# DAAP.net
KiCad netlist of a schematic drawn in EasyEDA
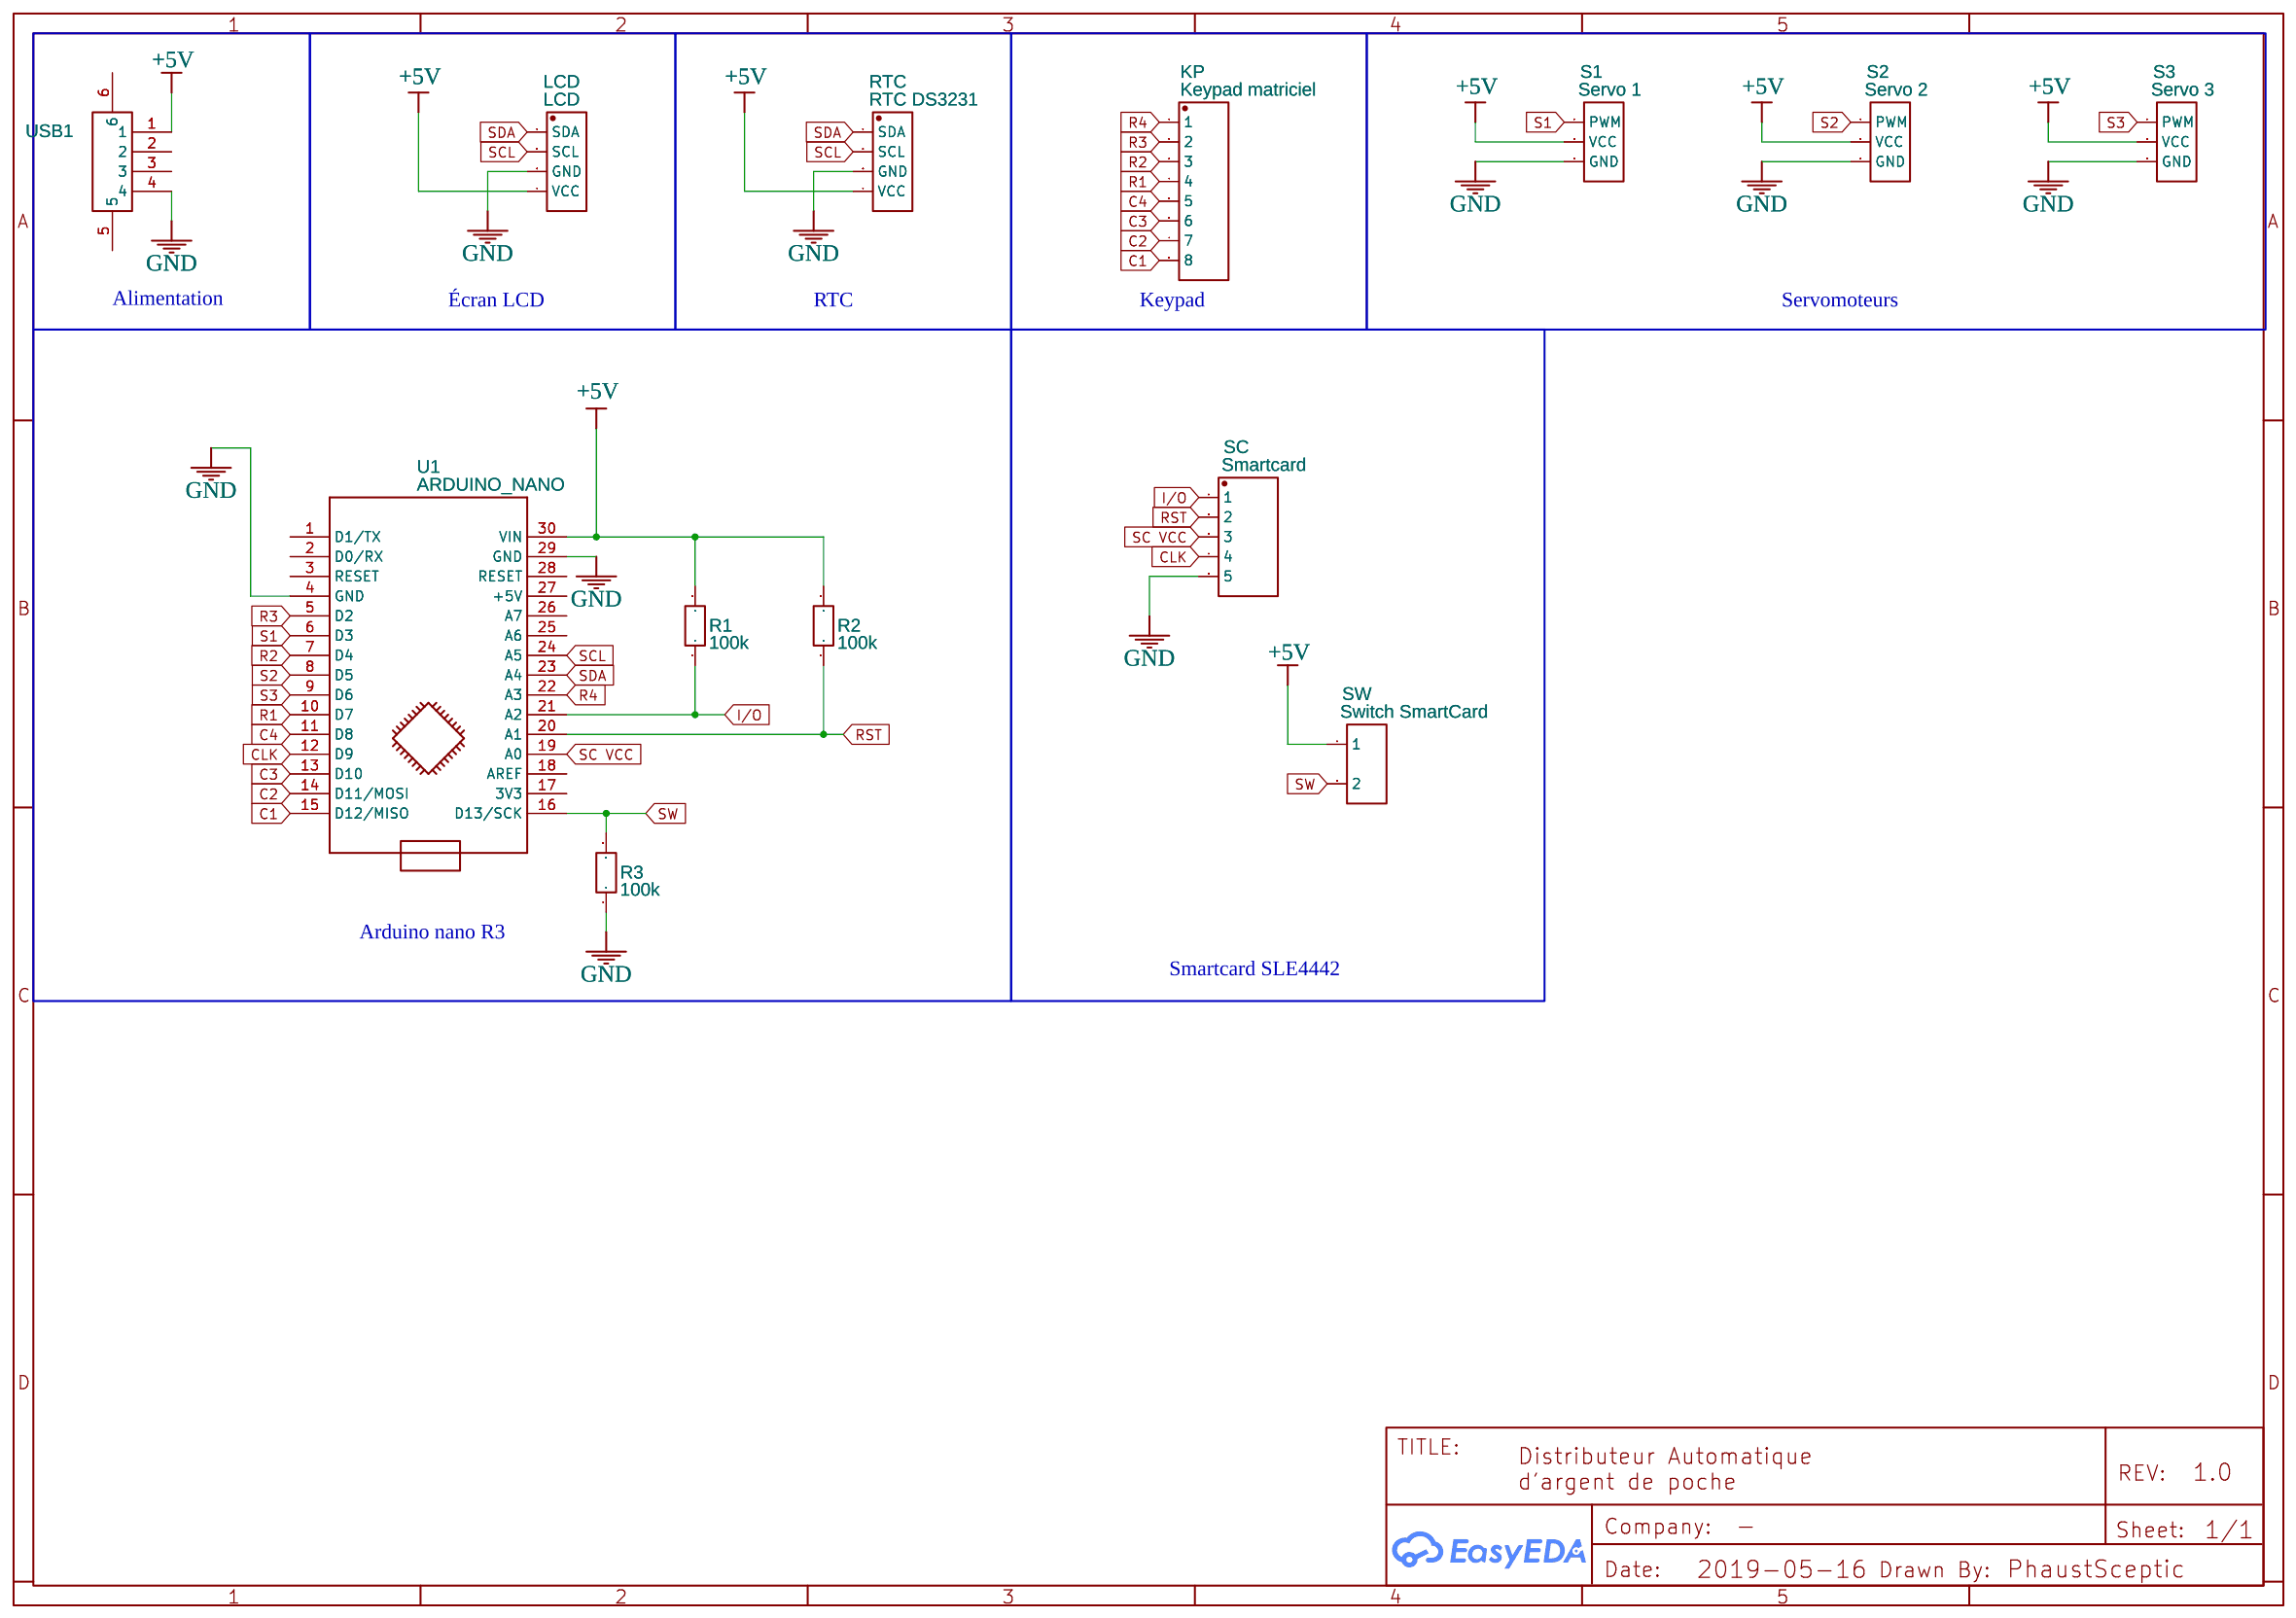
[diagram p0: schematic sheet]

(export (version "E")
  (design (tool "Eeschema 10.0.6"))
  (components
    (comp (ref "KP")
      (value "Keypad matriciel")
      (fields
        (field (name "BOM_Manufacturer Part") "210S-1*8P L=11.6MMGold-plated black")
        (field (name "BOM_Supplier Part") "C124381")
      )
      (libsource (lib "") (part "Unknown_600_90"))
    )
    (comp (ref "LCD")
      (value "LCD")
      (fields
        (field (name "BOM_Manufacturer Part") "210S-1*4P L=11.6MMGold-plated black")
        (field (name "BOM_Supplier Part") "C124378")
      )
      (libsource (lib "") (part "Unknown_275_75"))
    )
    (comp (ref "R1")
      (value "100k")
      (fields (field (name "BOM_Manufacturer Part") "?"))
      (libsource (lib "") (part "Res_AXIAL-0.3(1/8W)_EU"))
    )
    (comp (ref "R2")
      (value "100k")
      (fields (field (name "BOM_Manufacturer Part") "?"))
      (libsource (lib "") (part "Res_AXIAL-0.3(1/8W)_EU"))
    )
    (comp (ref "R3")
      (value "100k")
      (fields (field (name "BOM_Manufacturer Part") "?"))
      (libsource (lib "") (part "Res_AXIAL-0.3(1/8W)_EU"))
    )
    (comp (ref "RTC")
      (value "RTC DS3231")
      (fields
        (field (name "BOM_Manufacturer Part") "210S-1*4P L=11.6MMGold-plated black")
        (field (name "BOM_Supplier Part") "C124378")
      )
      (libsource (lib "") (part "Unknown_440_75"))
    )
    (comp (ref "S1")
      (value "Servo 1")
      (fields
        (field (name "BOM_Manufacturer Part") "Header2.54mm 1*3P")
        (field (name "BOM_Supplier Part") "C49257")
      )
      (libsource (lib "") (part "Unknown_800_65"))
    )
    (comp (ref "S2")
      (value "Servo 2")
      (fields
        (field (name "BOM_Manufacturer Part") "Header2.54mm 1*3P")
        (field (name "BOM_Supplier Part") "C49257")
      )
      (libsource (lib "") (part "Unknown_945_65"))
    )
    (comp (ref "S3")
      (value "Servo 3")
      (fields
        (field (name "BOM_Manufacturer Part") "Header2.54mm 1*3P")
        (field (name "BOM_Supplier Part") "C49257")
      )
      (libsource (lib "") (part "Unknown_1090_65"))
    )
    (comp (ref "SC")
      (value "Smartcard")
      (fields
        (field (name "BOM_Manufacturer Part") "210S-1*5P L=11.6MMGold-plated black")
        (field (name "BOM_Supplier Part") "C124379")
      )
      (libsource (lib "") (part "Unknown_620_265"))
    )
    (comp (ref "SW")
      (value "Switch SmartCard")
      (fields (field (name "BOM_Manufacturer Part") "826629-2") (field (name "BOM_Supplier Part") "C86471"))
      (libsource (lib "") (part "Unknown_680_380"))
    )
    (comp (ref "U1")
      (value "ARDUINO_NANO")
      (fields (field (name "BOM_Manufacturer Part") "?"))
      (libsource (lib "") (part "Unknown_210_340"))
    )
    (comp (ref "USB1")
      (value "USB-AF-90-14.4X13.6-H7.0-DIP")
      (fields (field (name "BOM_Supplier Part") "C46407"))
      (libsource (lib "") (part "Unknown_50_70"))
    )
  )
  (nets
    (net (code "1") (name "+5V") (class "Default")
      (node (ref "LCD") (pin "4") (pinfunction "VCC_4") (pintype "unspecified"))
      (node (ref "R1") (pin "2") (pinfunction "2_2") (pintype "unspecified"))
      (node (ref "R2") (pin "2") (pinfunction "2_2") (pintype "unspecified"))
      (node (ref "RTC") (pin "4") (pinfunction "VCC_4") (pintype "unspecified"))
      (node (ref "S1") (pin "2") (pinfunction "VCC_2") (pintype "input"))
      (node (ref "S2") (pin "2") (pinfunction "VCC_2") (pintype "input"))
      (node (ref "S3") (pin "2") (pinfunction "VCC_2") (pintype "input"))
      (node (ref "SW") (pin "1") (pinfunction "1_1") (pintype "unspecified"))
      (node (ref "U1") (pin "30") (pinfunction "VIN_30") (pintype "unspecified"))
      (node (ref "USB1") (pin "1") (pinfunction "1_1") (pintype "unspecified"))
    )
    (net (code "2") (name "C1") (class "Default")
      (node (ref "KP") (pin "8") (pinfunction "8_8") (pintype "unspecified"))
      (node (ref "U1") (pin "15") (pinfunction "D12/MISO_15") (pintype "unspecified"))
    )
    (net (code "3") (name "C2") (class "Default")
      (node (ref "KP") (pin "7") (pinfunction "7_7") (pintype "unspecified"))
      (node (ref "U1") (pin "14") (pinfunction "D11/MOSI_14") (pintype "unspecified"))
    )
    (net (code "4") (name "C3") (class "Default")
      (node (ref "KP") (pin "6") (pinfunction "6_6") (pintype "unspecified"))
      (node (ref "U1") (pin "13") (pinfunction "D10_13") (pintype "unspecified"))
    )
    (net (code "5") (name "C4") (class "Default")
      (node (ref "KP") (pin "5") (pinfunction "5_5") (pintype "unspecified"))
      (node (ref "U1") (pin "11") (pinfunction "D8_11") (pintype "unspecified"))
    )
    (net (code "6") (name "CLK") (class "Default")
      (node (ref "SC") (pin "4") (pinfunction "4_4") (pintype "unspecified"))
      (node (ref "U1") (pin "12") (pinfunction "D9_12") (pintype "unspecified"))
    )
    (net (code "7") (name "GND") (class "Default")
      (node (ref "LCD") (pin "3") (pinfunction "GND_3") (pintype "unspecified"))
      (node (ref "R3") (pin "1") (pinfunction "1_1") (pintype "unspecified"))
      (node (ref "RTC") (pin "3") (pinfunction "GND_3") (pintype "unspecified"))
      (node (ref "S1") (pin "3") (pinfunction "GND_3") (pintype "input"))
      (node (ref "S2") (pin "3") (pinfunction "GND_3") (pintype "input"))
      (node (ref "S3") (pin "3") (pinfunction "GND_3") (pintype "input"))
      (node (ref "SC") (pin "5") (pinfunction "5_5") (pintype "unspecified"))
      (node (ref "U1") (pin "29") (pinfunction "GND_29") (pintype "unspecified"))
      (node (ref "U1") (pin "4") (pinfunction "GND_4") (pintype "unspecified"))
      (node (ref "USB1") (pin "4") (pinfunction "4_4") (pintype "unspecified"))
    )
    (net (code "8") (name "I{slash}O") (class "Default")
      (node (ref "R1") (pin "1") (pinfunction "1_1") (pintype "unspecified"))
      (node (ref "SC") (pin "1") (pinfunction "1_1") (pintype "unspecified"))
      (node (ref "U1") (pin "21") (pinfunction "A2_21") (pintype "unspecified"))
    )
    (net (code "9") (name "R1") (class "Default")
      (node (ref "KP") (pin "4") (pinfunction "4_4") (pintype "unspecified"))
      (node (ref "U1") (pin "10") (pinfunction "D7_10") (pintype "unspecified"))
    )
    (net (code "10") (name "R2") (class "Default")
      (node (ref "KP") (pin "3") (pinfunction "3_3") (pintype "unspecified"))
      (node (ref "U1") (pin "7") (pinfunction "D4_7") (pintype "unspecified"))
    )
    (net (code "11") (name "R3") (class "Default")
      (node (ref "KP") (pin "2") (pinfunction "2_2") (pintype "unspecified"))
      (node (ref "U1") (pin "5") (pinfunction "D2_5") (pintype "unspecified"))
    )
    (net (code "12") (name "R4") (class "Default")
      (node (ref "KP") (pin "1") (pinfunction "1_1") (pintype "unspecified"))
      (node (ref "U1") (pin "22") (pinfunction "A3_22") (pintype "unspecified"))
    )
    (net (code "13") (name "RST") (class "Default")
      (node (ref "R2") (pin "1") (pinfunction "1_1") (pintype "unspecified"))
      (node (ref "SC") (pin "2") (pinfunction "2_2") (pintype "unspecified"))
      (node (ref "U1") (pin "20") (pinfunction "A1_20") (pintype "unspecified"))
    )
    (net (code "14") (name "S1") (class "Default")
      (node (ref "S1") (pin "1") (pinfunction "PWM_1") (pintype "input"))
      (node (ref "U1") (pin "6") (pinfunction "D3_6") (pintype "unspecified"))
    )
    (net (code "15") (name "S2") (class "Default")
      (node (ref "S2") (pin "1") (pinfunction "PWM_1") (pintype "input"))
      (node (ref "U1") (pin "8") (pinfunction "D5_8") (pintype "unspecified"))
    )
    (net (code "16") (name "S3") (class "Default")
      (node (ref "S3") (pin "1") (pinfunction "PWM_1") (pintype "input"))
      (node (ref "U1") (pin "9") (pinfunction "D6_9") (pintype "unspecified"))
    )
    (net (code "17") (name "SC VCC") (class "Default")
      (node (ref "SC") (pin "3") (pinfunction "3_3") (pintype "unspecified"))
      (node (ref "U1") (pin "19") (pinfunction "A0_19") (pintype "unspecified"))
    )
    (net (code "18") (name "SCL") (class "Default")
      (node (ref "LCD") (pin "2") (pinfunction "SCL_2") (pintype "unspecified"))
      (node (ref "RTC") (pin "2") (pinfunction "SCL_2") (pintype "unspecified"))
      (node (ref "U1") (pin "24") (pinfunction "A5_24") (pintype "unspecified"))
    )
    (net (code "19") (name "SDA") (class "Default")
      (node (ref "LCD") (pin "1") (pinfunction "SDA_1") (pintype "unspecified"))
      (node (ref "RTC") (pin "1") (pinfunction "SDA_1") (pintype "unspecified"))
      (node (ref "U1") (pin "23") (pinfunction "A4_23") (pintype "unspecified"))
    )
    (net (code "20") (name "SW") (class "Default")
      (node (ref "R3") (pin "2") (pinfunction "2_2") (pintype "unspecified"))
      (node (ref "SW") (pin "2") (pinfunction "2_2") (pintype "unspecified"))
      (node (ref "U1") (pin "16") (pinfunction "D13/SCK_16") (pintype "unspecified"))
    )
    (net (code "21") (name "unconnected-(U1-+5V-Pad27)") (class "Default")
      (node (ref "U1") (pin "27") (pinfunction "+5V_27") (pintype "unspecified"))
    )
    (net (code "22") (name "unconnected-(U1-3V3-Pad17)") (class "Default")
      (node (ref "U1") (pin "17") (pinfunction "3V3_17") (pintype "unspecified"))
    )
    (net (code "23") (name "unconnected-(U1-A6-Pad25)") (class "Default")
      (node (ref "U1") (pin "25") (pinfunction "A6_25") (pintype "unspecified"))
    )
    (net (code "24") (name "unconnected-(U1-A7-Pad26)") (class "Default")
      (node (ref "U1") (pin "26") (pinfunction "A7_26") (pintype "unspecified"))
    )
    (net (code "25") (name "unconnected-(U1-AREF-Pad18)") (class "Default")
      (node (ref "U1") (pin "18") (pinfunction "AREF_18") (pintype "unspecified"))
    )
    (net (code "26") (name "unconnected-(U1-D0{slash}RX-Pad2)") (class "Default")
      (node (ref "U1") (pin "2") (pinfunction "D0/RX_2") (pintype "unspecified"))
    )
    (net (code "27") (name "unconnected-(U1-D1{slash}TX-Pad1)") (class "Default")
      (node (ref "U1") (pin "1") (pinfunction "D1/TX_1") (pintype "unspecified"))
    )
    (net (code "28") (name "unconnected-(U1-RESET-Pad3)") (class "Default")
      (node (ref "U1") (pin "3") (pinfunction "RESET_3") (pintype "unspecified"))
    )
    (net (code "29") (name "unconnected-(U1-RESET-Pad28)") (class "Default")
      (node (ref "U1") (pin "28") (pinfunction "RESET_28") (pintype "unspecified"))
    )
    (net (code "30") (name "unconnected-(USB1-Pad2)") (class "Default")
      (node (ref "USB1") (pin "2") (pinfunction "2_2") (pintype "unspecified"))
    )
    (net (code "31") (name "unconnected-(USB1-Pad3)") (class "Default")
      (node (ref "USB1") (pin "3") (pinfunction "3_3") (pintype "unspecified"))
    )
    (net (code "32") (name "unconnected-(USB1-Pad5)") (class "Default")
      (node (ref "USB1") (pin "5") (pinfunction "5_5") (pintype "unspecified"))
    )
    (net (code "33") (name "unconnected-(USB1-Pad6)") (class "Default")
      (node (ref "USB1") (pin "6") (pinfunction "6_6") (pintype "unspecified"))
    )
  )
)
